# I2C_Keypad.net
KiCad netlist of a schematic drawn in Altium Designer
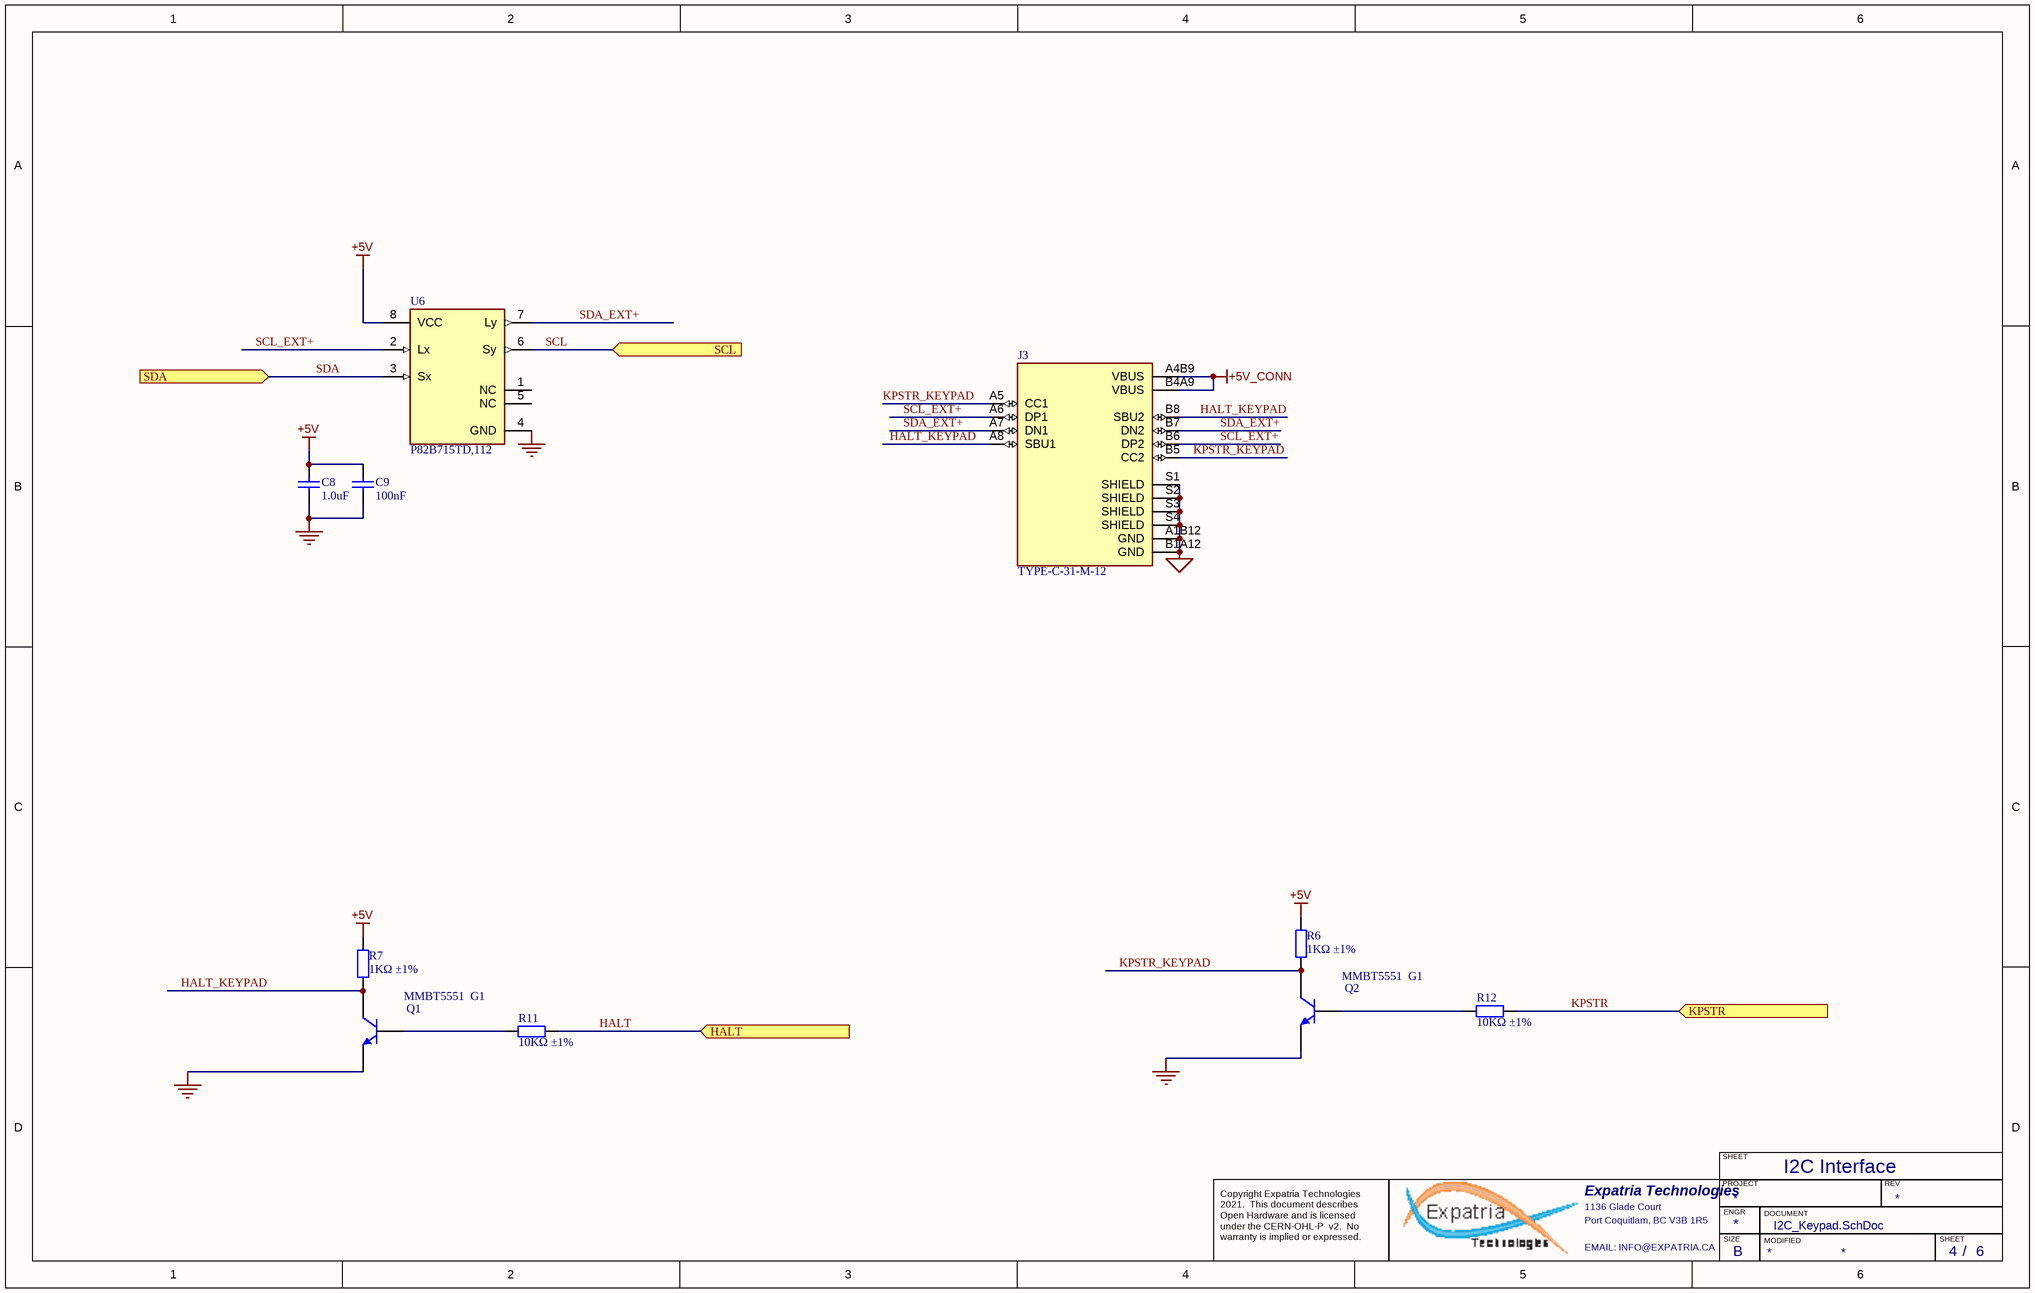
[diagram p0: I2C_Keypad.SchDoc]

(export (version "E")
  (design (tool "Eeschema 10.0.6"))
  (components
    (comp (ref "C8")
      (value "1.0uF")
      (footprint "0402_C")
      (description "Chip capacitor")
      (fields
        (field (name "MANUFACTURER") "Samsung Electro-Mechanics")
        (field (name "PARTNUMBER") "CL05A105KA5NQNC")
      )
      (libsource (lib "Cap") (part "0402 1.0uF (105) 10% 25V"))
    )
    (comp (ref "C9")
      (value "100nF")
      (footprint "0402_C")
      (description "Chip capacitors")
      (fields
        (field (name "MANUFACTURER") "Samsung Electro-Mechanics")
        (field (name "PARTNUMBER") "CL05B104KO5NNNC")
      )
      (libsource (lib "Cap") (part "0402 100nF (104) 10% 16V"))
    )
    (comp (ref "J3")
      (value "TYPE-C-31-M-12")
      (footprint "HRO_TYPE-C-31-M-12")
      (description "USB Connectors 24 Receptacle 1 8.94*7.3mm RoHS")
      (fields (field (name "MF") "HRO Electronics Co., Ltd."))
      (libsource (lib "Universal_CNC_Breakout") (part "TYPE-C-31-M-12"))
    )
    (comp (ref "Q1")
      (value "MMBT5551  G1")
      (footprint "SOT-23(SOT-23-3)")
      (description "三极管")
      (libsource (lib "Transistor_NPN") (part "SOT-23 MMBT5551  G1"))
    )
    (comp (ref "Q2")
      (value "MMBT5551  G1")
      (footprint "SOT-23(SOT-23-3)")
      (description "三极管")
      (libsource (lib "Transistor_NPN") (part "SOT-23 MMBT5551  G1"))
    )
    (comp (ref "R6")
      (value "1KΩ ±1%")
      (footprint "0402_R")
      (description "Chip resistor")
      (fields (field (name "MANUFACTURER") "Uniroyal Elec") (field (name "PARTNUMBER") "0402WGF1001TCE"))
      (libsource (lib "RES") (part "0402 1K (1001) 1%"))
    )
    (comp (ref "R7")
      (value "1KΩ ±1%")
      (footprint "0402_R")
      (description "Chip resistor")
      (fields (field (name "MANUFACTURER") "Uniroyal Elec") (field (name "PARTNUMBER") "0402WGF1001TCE"))
      (libsource (lib "RES") (part "0402 1K (1001) 1%"))
    )
    (comp (ref "R11")
      (value "10KΩ ±1%")
      (footprint "0402_R")
      (description "Chip resistor")
      (fields (field (name "MANUFACTURER") "Uniroyal Elec") (field (name "PARTNUMBER") "0402WGF1002TCE"))
      (libsource (lib "") (part "0402 10K (1002) 1%_1"))
    )
    (comp (ref "R12")
      (value "10KΩ ±1%")
      (footprint "0402_R")
      (description "Chip resistor")
      (fields (field (name "MANUFACTURER") "Uniroyal Elec") (field (name "PARTNUMBER") "0402WGF1002TCE"))
      (libsource (lib "RES") (part "0402 10K (1002) 1%"))
    )
    (comp (ref "U6")
      (value "P82B715TD,112")
      (footprint "FP-SOT96-1-MFG")
      (description "IC REDRIVER I2C 1CH 400KHZ 8SO")
      (fields
        (field (name "MANUFACTURER") "NXP Semicon")
        (field (name "MANUFACTURER_PART_NUMBER") "P82B715TD,118")
      )
      (libsource (lib "Altium Content Vault") (part "feec727f4072afc4f94d4e12e138974"))
    )
  )
  (nets
    (net (code "1") (name "+5V") (class "Default")
      (node (ref "C8") (pin "2") (pinfunction "2_2") (pintype "passive"))
      (node (ref "C9") (pin "2") (pinfunction "2_2") (pintype "passive"))
      (node (ref "R6") (pin "1") (pinfunction "1_1") (pintype "passive"))
      (node (ref "R7") (pin "1") (pinfunction "1_1") (pintype "passive"))
      (node (ref "U6") (pin "8") (pinfunction "VCC_8") (pintype "power_in"))
    )
    (net (code "2") (name "+5V_CONN") (class "Default")
      (node (ref "J3") (pin "A4B9") (pinfunction "VBUS_A4B9") (pintype "power_in"))
      (node (ref "J3") (pin "B4A9") (pinfunction "VBUS_B4A9") (pintype "power_in"))
    )
    (net (code "3") (name "/HALT") (class "Default")
      (node (ref "R11") (pin "2") (pinfunction "2_2") (pintype "passive"))
    )
    (net (code "4") (name "/HALT_KEYPAD") (class "Default")
      (node (ref "J3") (pin "A8") (pinfunction "SBU1_A8") (pintype "bidirectional"))
      (node (ref "J3") (pin "B8") (pinfunction "SBU2_B8") (pintype "bidirectional"))
      (node (ref "Q1") (pin "3") (pinfunction "C_3") (pintype "passive"))
      (node (ref "R7") (pin "2") (pinfunction "2_2") (pintype "passive"))
    )
    (net (code "5") (name "/KPSTR") (class "Default")
      (node (ref "R12") (pin "1") (pinfunction "1_1") (pintype "passive"))
    )
    (net (code "6") (name "/KPSTR_KEYPAD") (class "Default")
      (node (ref "J3") (pin "A5") (pinfunction "CC1_A5") (pintype "bidirectional"))
      (node (ref "J3") (pin "B5") (pinfunction "CC2_B5") (pintype "bidirectional"))
      (node (ref "Q2") (pin "3") (pinfunction "C_3") (pintype "passive"))
      (node (ref "R6") (pin "2") (pinfunction "2_2") (pintype "passive"))
    )
    (net (code "7") (name "/SCL") (class "Default")
      (node (ref "U6") (pin "6") (pinfunction "Sy_6") (pintype "output"))
    )
    (net (code "8") (name "/SCL_EXT+") (class "Default")
      (node (ref "J3") (pin "A6") (pinfunction "DP1_A6") (pintype "bidirectional"))
      (node (ref "J3") (pin "B6") (pinfunction "DP2_B6") (pintype "bidirectional"))
      (node (ref "U6") (pin "2") (pinfunction "Lx_2") (pintype "input"))
    )
    (net (code "9") (name "/SDA") (class "Default")
      (node (ref "U6") (pin "3") (pinfunction "Sx_3") (pintype "input"))
    )
    (net (code "10") (name "/SDA_EXT+") (class "Default")
      (node (ref "J3") (pin "A7") (pinfunction "DN1_A7") (pintype "bidirectional"))
      (node (ref "J3") (pin "B7") (pinfunction "DN2_B7") (pintype "bidirectional"))
      (node (ref "U6") (pin "7") (pinfunction "Ly_7") (pintype "output"))
    )
    (net (code "11") (name "GND") (class "Default")
      (node (ref "C8") (pin "1") (pinfunction "1_1") (pintype "passive"))
      (node (ref "C9") (pin "1") (pinfunction "1_1") (pintype "passive"))
      (node (ref "Q1") (pin "2") (pinfunction "E_2") (pintype "passive"))
      (node (ref "Q2") (pin "2") (pinfunction "E_2") (pintype "passive"))
      (node (ref "U6") (pin "4") (pinfunction "GND_4") (pintype "power_in"))
    )
    (net (code "12") (name "GND_CONN") (class "Default")
      (node (ref "J3") (pin "A1B12") (pinfunction "GND_A1B12") (pintype "power_in"))
      (node (ref "J3") (pin "B1A12") (pinfunction "GND_B1A12") (pintype "power_in"))
      (node (ref "J3") (pin "S1") (pinfunction "SHIELD_S1") (pintype "passive"))
      (node (ref "J3") (pin "S2") (pinfunction "SHIELD_S2") (pintype "passive"))
      (node (ref "J3") (pin "S3") (pinfunction "SHIELD_S3") (pintype "passive"))
      (node (ref "J3") (pin "S4") (pinfunction "SHIELD_S4") (pintype "passive"))
    )
    (net (code "13") (name "Net-(Q1-B)") (class "Default")
      (node (ref "Q1") (pin "1") (pinfunction "B_1") (pintype "passive"))
      (node (ref "R11") (pin "1") (pinfunction "1_1") (pintype "passive"))
    )
    (net (code "14") (name "Net-(Q2-B)") (class "Default")
      (node (ref "Q2") (pin "1") (pinfunction "B_1") (pintype "passive"))
      (node (ref "R12") (pin "2") (pinfunction "2_2") (pintype "passive"))
    )
    (net (code "15") (name "unconnected-(U6-NC-Pad1)") (class "Default")
      (node (ref "U6") (pin "1") (pinfunction "NC_1") (pintype "passive"))
    )
    (net (code "16") (name "unconnected-(U6-NC-Pad5)") (class "Default")
      (node (ref "U6") (pin "5") (pinfunction "NC_5") (pintype "passive"))
    )
  )
)
